# nanopositioner.net
KiCad netlist of a schematic drawn in EAGLE
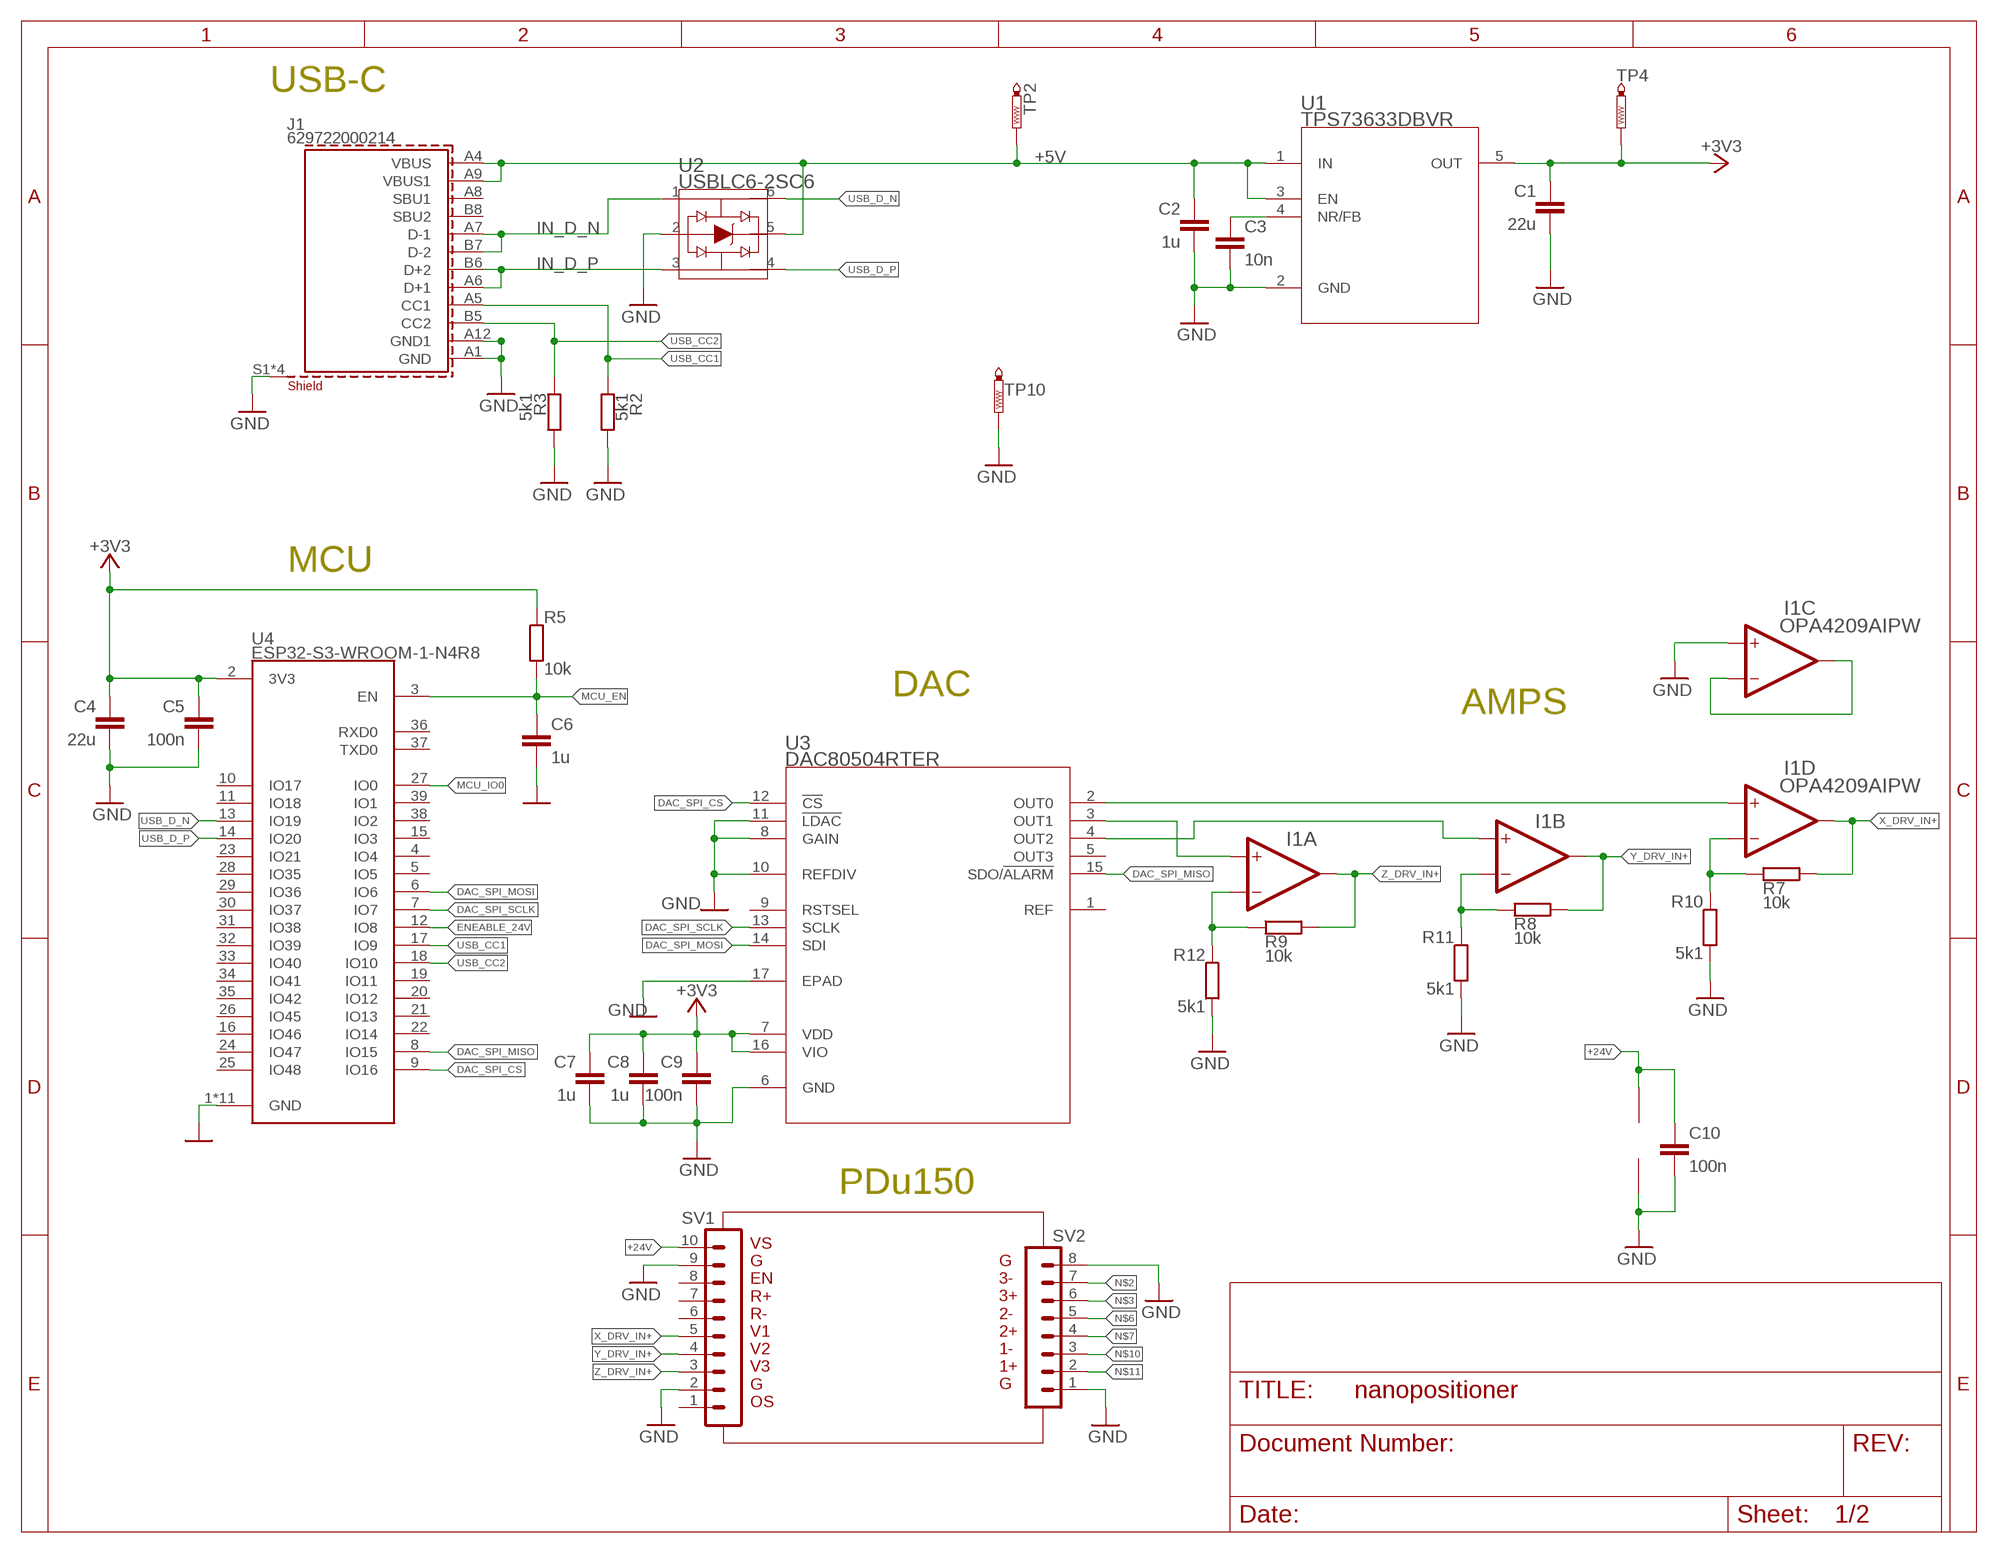
[diagram p0: schematic, sheet 1]
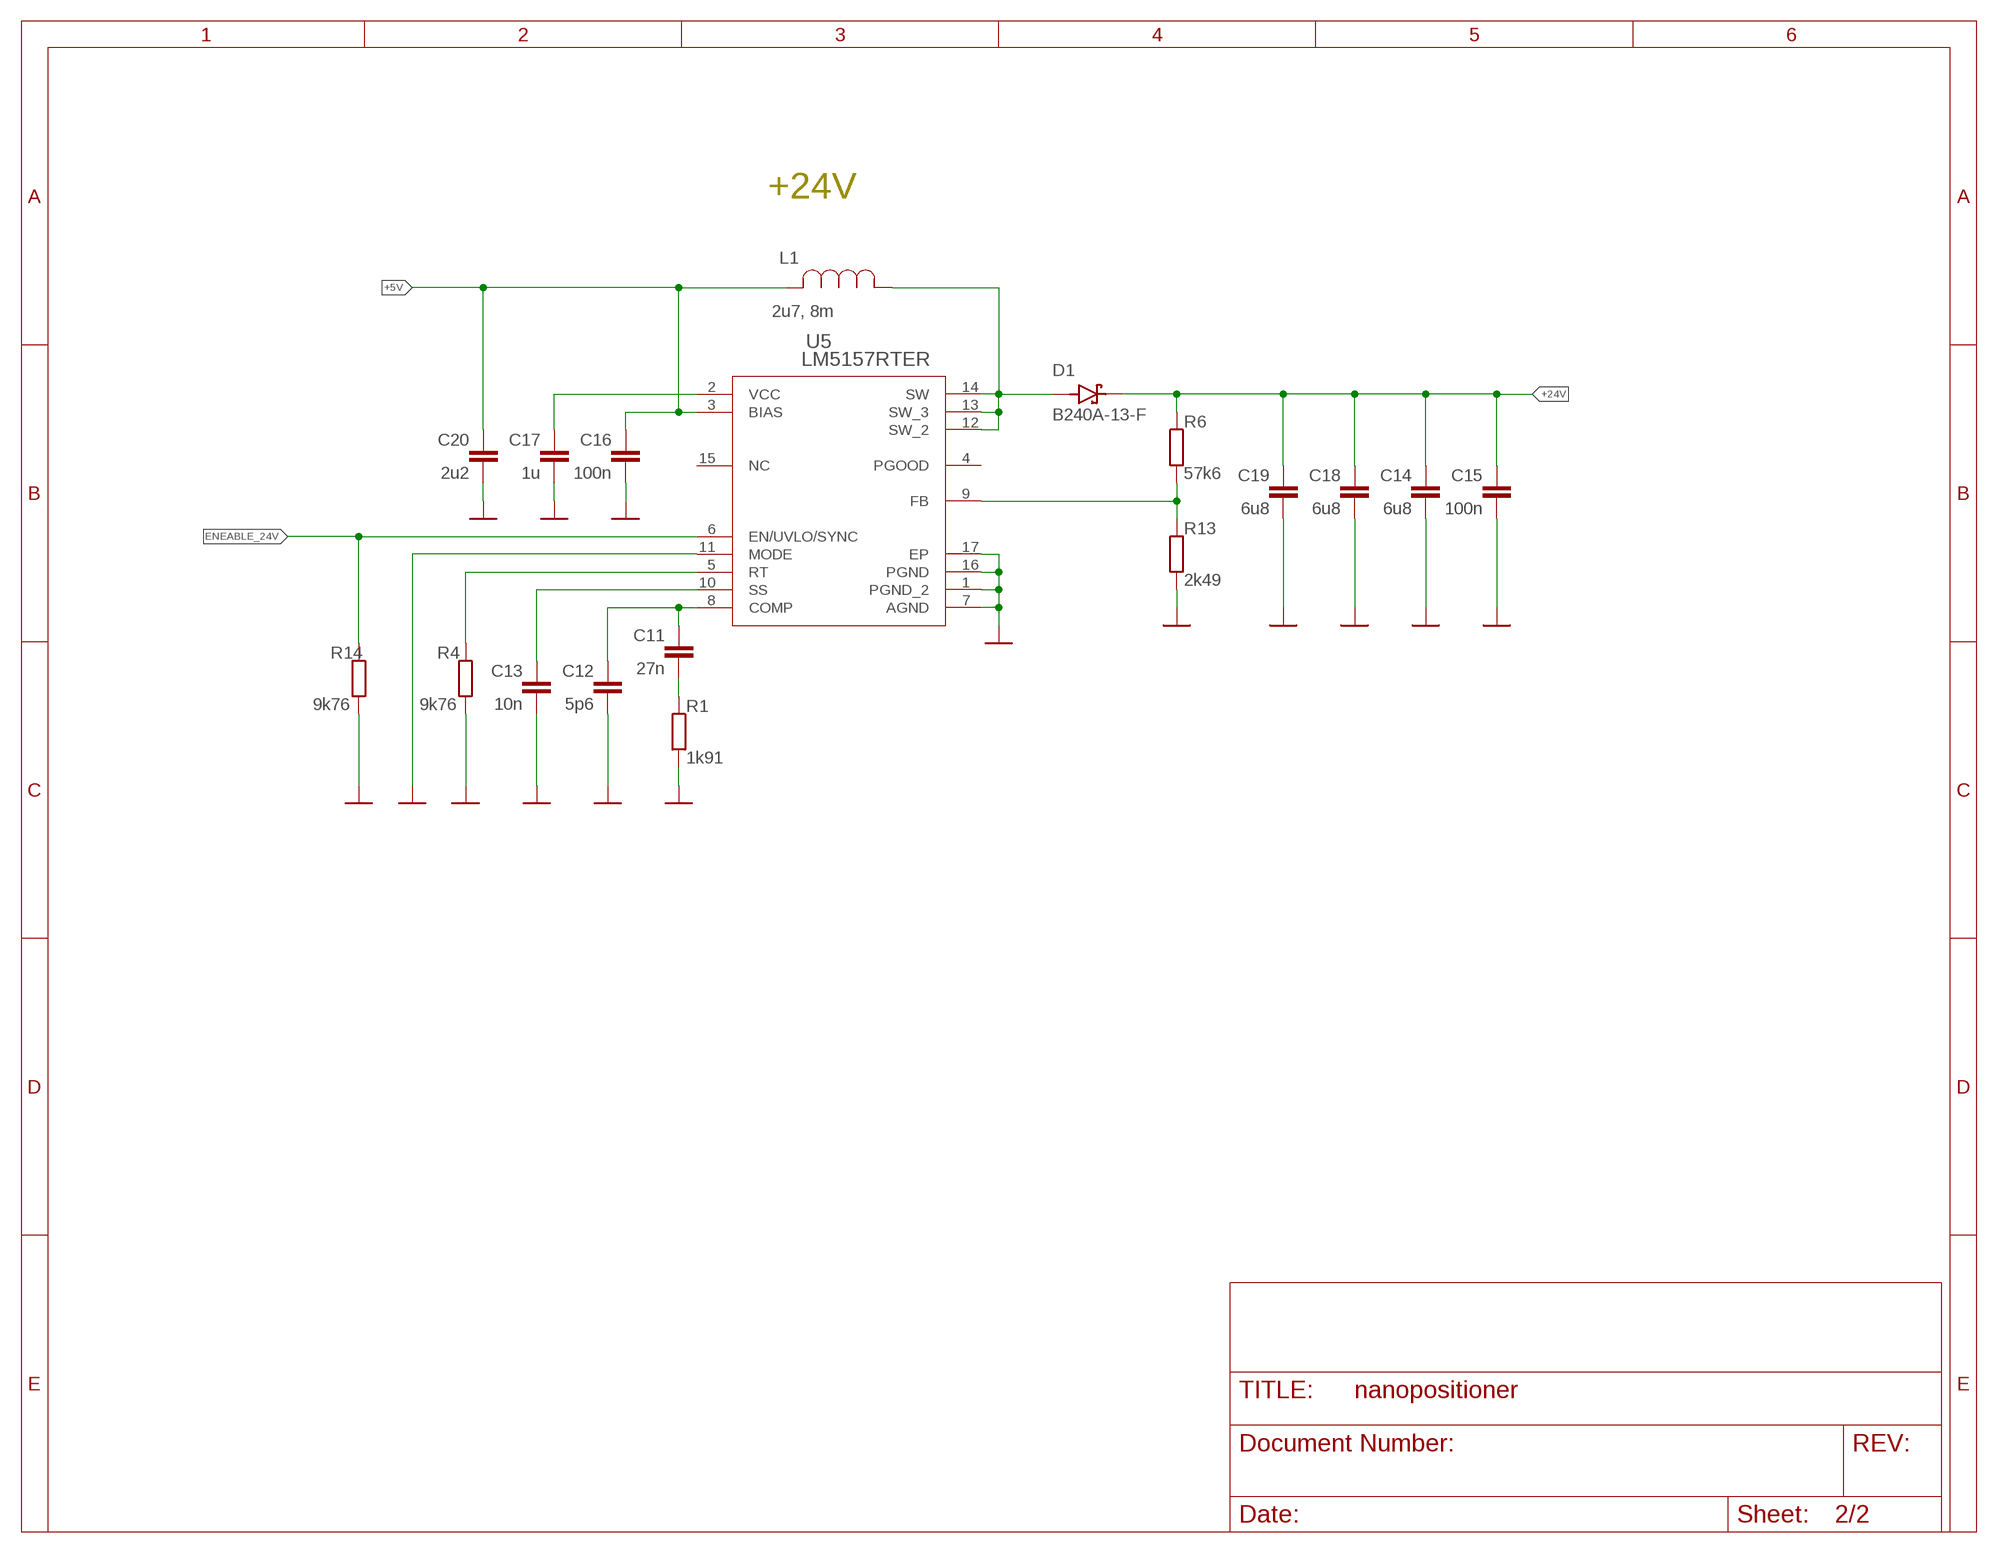
[diagram p1: schematic, sheet 2]

(export (version "E")
  (design (tool "Eeschema 10.0.6"))
  (components
    (comp (ref "C1")
      (value "22u")
      (footprint "eagle-import:C0603")
      (fields (field (name "MPN") "CL10A226MP8NUNE"))
      (libsource (lib "eagle-import") (part "C-EUC0603"))
    )
    (comp (ref "C2")
      (value "1u")
      (footprint "eagle-import:C0402")
      (fields (field (name "MPN") "GRM155R61E105MA12D"))
      (libsource (lib "eagle-import") (part "C-EUC0402"))
    )
    (comp (ref "C3")
      (value "10n")
      (footprint "eagle-import:C0402")
      (fields (field (name "MPN") "GCM155R71H103KA55D"))
      (libsource (lib "eagle-import") (part "C-EUC0402"))
    )
    (comp (ref "C4")
      (value "22u")
      (footprint "eagle-import:C0603")
      (fields (field (name "MPN") "CL10A226MP8NUNE"))
      (libsource (lib "eagle-import") (part "C-EUC0603"))
    )
    (comp (ref "C5")
      (value "100n")
      (footprint "eagle-import:C0402")
      (fields (field (name "MPN") "GRM155R71H104KE14D"))
      (libsource (lib "eagle-import") (part "C-EUC0402"))
    )
    (comp (ref "C6")
      (value "1u")
      (footprint "eagle-import:C0402")
      (fields (field (name "MPN") "GRM155R61E105MA12D"))
      (libsource (lib "eagle-import") (part "C-EUC0402"))
    )
    (comp (ref "C7")
      (value "1u")
      (footprint "eagle-import:C0402")
      (fields (field (name "MPN") "GRM155R61E105MA12D"))
      (libsource (lib "eagle-import") (part "C-EUC0402"))
    )
    (comp (ref "C8")
      (value "1u")
      (footprint "eagle-import:C0402")
      (fields (field (name "MPN") "GRM155R61E105MA12D"))
      (libsource (lib "eagle-import") (part "C-EUC0402"))
    )
    (comp (ref "C9")
      (value "100n")
      (footprint "eagle-import:C0402")
      (fields (field (name "MPN") "GRM155R71H104KE14D"))
      (libsource (lib "eagle-import") (part "C-EUC0402"))
    )
    (comp (ref "C10")
      (value "100n")
      (footprint "eagle-import:C0402")
      (fields (field (name "MPN") "GRM155R71H104KE14D"))
      (libsource (lib "eagle-import") (part "C-EUC0402"))
    )
    (comp (ref "I1")
      (value "OPA4209AIPW")
      (footprint "eagle-import:PW14")
      (fields
        (field (name "MPN") "OPA4209AIPW")
        (field (name "SPICEPREFIX") "J")
        (field (name "COPYRIGHT") "Copyright (C) 2024 Ultra Librarian. All rights reserved.")
      )
      (libsource (lib "eagle-import") (part "OPA4209AIPW"))
    )
    (comp (ref "J1")
      (value "629722000214")
      (footprint "eagle-import:629722000214")
      (fields (field (name "MPN") "12402012E212A"))
      (libsource (lib "eagle-import") (part "629722000214"))
    )
    (comp (ref "R2")
      (value "5k1")
      (footprint "eagle-import:R0402")
      (fields (field (name "MPN") "ERA-2AEB512X"))
      (libsource (lib "eagle-import") (part "R-EU_R0402"))
    )
    (comp (ref "R3")
      (value "5k1")
      (footprint "eagle-import:R0402")
      (fields (field (name "MPN") "ERA-2AEB512X"))
      (libsource (lib "eagle-import") (part "R-EU_R0402"))
    )
    (comp (ref "R5")
      (value "10k")
      (footprint "eagle-import:R0402")
      (fields (field (name "MPN") "ERA-2AEB103X"))
      (libsource (lib "eagle-import") (part "R-EU_R0402"))
    )
    (comp (ref "R7")
      (value "10k")
      (footprint "eagle-import:R0402")
      (fields (field (name "MPN") "ERA-2AEB103X"))
      (libsource (lib "eagle-import") (part "R-EU_R0402"))
    )
    (comp (ref "R8")
      (value "10k")
      (footprint "eagle-import:R0402")
      (fields (field (name "MPN") "ERA-2AEB103X"))
      (libsource (lib "eagle-import") (part "R-EU_R0402"))
    )
    (comp (ref "R9")
      (value "10k")
      (footprint "eagle-import:R0402")
      (fields (field (name "MPN") "ERA-2AEB103X"))
      (libsource (lib "eagle-import") (part "R-EU_R0402"))
    )
    (comp (ref "R10")
      (value "5k1")
      (footprint "eagle-import:R0402")
      (fields (field (name "MPN") "ERA-2AEB512X"))
      (libsource (lib "eagle-import") (part "R-EU_R0402"))
    )
    (comp (ref "R11")
      (value "5k1")
      (footprint "eagle-import:R0402")
      (fields (field (name "MPN") "ERA-2AEB512X"))
      (libsource (lib "eagle-import") (part "R-EU_R0402"))
    )
    (comp (ref "R12")
      (value "5k1")
      (footprint "eagle-import:R0402")
      (fields (field (name "MPN") "ERA-2AEB512X"))
      (libsource (lib "eagle-import") (part "R-EU_R0402"))
    )
    (comp (ref "SV1")
      (value "MA10-1")
      (footprint "eagle-import:MA10-1")
      (libsource (lib "eagle-import") (part "MA10-1"))
    )
    (comp (ref "SV2")
      (value "MA08-1")
      (footprint "eagle-import:MA08-1")
      (libsource (lib "eagle-import") (part "MA08-1"))
    )
    (comp (ref "TP2")
      (value "PTR1PAD1-13")
      (footprint "eagle-import:P1-13")
      (libsource (lib "eagle-import") (part "PTR1PAD1-13"))
    )
    (comp (ref "TP4")
      (value "PTR1PAD1-13")
      (footprint "eagle-import:P1-13")
      (libsource (lib "eagle-import") (part "PTR1PAD1-13"))
    )
    (comp (ref "TP10")
      (value "PTR1PAD1-13")
      (footprint "eagle-import:P1-13")
      (libsource (lib "eagle-import") (part "PTR1PAD1-13"))
    )
    (comp (ref "U1")
      (value "TPS73633DBVR")
      (footprint "eagle-import:DBV5")
      (fields
        (field (name "MANUFACTURER_PART_NUMBER") "TPS73601DBVR")
        (field (name "COPYRIGHT") "Copyright (C) 2023 Ultra Librarian. All rights reserved.")
      )
      (libsource (lib "eagle-import") (part "TPS73633DBVR"))
    )
    (comp (ref "U2")
      (value "USBLC6-2SC6")
      (footprint "eagle-import:SOT23-6L_STM")
      (fields (field (name "COPYRIGHT") "Copyright (C) 2023 Ultra Librarian. All rights reserved."))
      (libsource (lib "eagle-import") (part "USBLC6-2SC6"))
    )
    (comp (ref "U3")
      (value "DAC80504RTER")
      (footprint "eagle-import:RTE16_TEX")
      (fields
        (field (name "MPN") "DAC80504RTET")
        (field (name "COPYRIGHT") "Copyright (C) 2024 Ultra Librarian. All rights reserved.")
      )
      (libsource (lib "eagle-import") (part "DAC80504RTER"))
    )
    (comp (ref "U4")
      (value "ESP32-S3-WROOM-1-N4R8")
      (footprint "eagle-import:XCVR_ESP32S3WROOM1N8R8")
      (fields
        (field (name "MF") "Espressif Systems")
        (field (name "MP") "ESP32-S3-WROOM-1-N8R8")
        (field (name "MPN") "ESP32-S3-WROOM-1-N4")
      )
      (libsource (lib "eagle-import") (part "ESP32-S3-WROOM-1-N4R8"))
    )
    (comp (ref "C11")
      (value "27n")
      (footprint "eagle-import:C0402")
      (fields (field (name "MPN") "GRM155R71A273KA01D"))
      (libsource (lib "eagle-import") (part "C-EUC0402"))
    )
    (comp (ref "C12")
      (value "5p6")
      (footprint "eagle-import:C0402")
      (fields (field (name "MPN") "GRM1555C1H5R6CA01D"))
      (libsource (lib "eagle-import") (part "C-EUC0402"))
    )
    (comp (ref "C13")
      (value "10n")
      (footprint "eagle-import:C0402")
      (fields (field (name "MPN") "GRM033R70J103KA01D"))
      (libsource (lib "eagle-import") (part "C-EUC0402"))
    )
    (comp (ref "C14")
      (value "6u8")
      (footprint "eagle-import:C1206")
      (fields (field (name "MPN") "C3216X5R1H685K160AB"))
      (libsource (lib "eagle-import") (part "C-EUC1206"))
    )
    (comp (ref "C15")
      (value "100n")
      (footprint "eagle-import:C0603")
      (fields (field (name "MPN") "CGA3E2X7R1H104K080AA"))
      (libsource (lib "eagle-import") (part "C-EUC0603"))
    )
    (comp (ref "C16")
      (value "100n")
      (footprint "eagle-import:C0603")
      (fields (field (name "MPN") "KGM21NR71E104KT"))
      (libsource (lib "eagle-import") (part "C-EUC0603"))
    )
    (comp (ref "C17")
      (value "1u")
      (footprint "eagle-import:C0402")
      (fields (field (name "MPN") "EMK107B7105KA-T"))
      (libsource (lib "eagle-import") (part "C-EUC0402"))
    )
    (comp (ref "C18")
      (value "6u8")
      (footprint "eagle-import:C1206")
      (fields (field (name "MPN") "C3216X5R1H685K160AB"))
      (libsource (lib "eagle-import") (part "C-EUC1206"))
    )
    (comp (ref "C19")
      (value "6u8")
      (footprint "eagle-import:C1206")
      (fields (field (name "MPN") "C3216X5R1H685K160AB"))
      (libsource (lib "eagle-import") (part "C-EUC1206"))
    )
    (comp (ref "C20")
      (value "2u2")
      (footprint "eagle-import:C0805")
      (fields (field (name "MPN") "GRM21BR71A225KA01L"))
      (libsource (lib "eagle-import") (part "C-EUC0805"))
    )
    (comp (ref "D1")
      (value "B240A-13-F")
      (footprint "eagle-import:DIOM5226X230N")
      (fields (field (name "MANUFACTURER") "Diodes"))
      (libsource (lib "eagle-import") (part "B240A-13-F"))
    )
    (comp (ref "L1")
      (value "2u7, 8m")
      (footprint "eagle-import:IND_BOURNS_SDR1307")
      (fields (field (name "MPN") "SDR1307-2R7ML"))
      (libsource (lib "eagle-import") (part "SDR1307-2R7ML"))
    )
    (comp (ref "R1")
      (value "1k91")
      (footprint "eagle-import:R0402")
      (fields (field (name "MPN") "CRCW04021K91FKED"))
      (libsource (lib "eagle-import") (part "R-EU_R0402"))
    )
    (comp (ref "R4")
      (value "9k76")
      (footprint "eagle-import:R0402")
      (fields (field (name "MPN") "CRCW04029K76FKED"))
      (libsource (lib "eagle-import") (part "R-EU_R0402"))
    )
    (comp (ref "R6")
      (value "57k6")
      (footprint "eagle-import:R0402")
      (fields (field (name "MPN") "CRCW040257K6FKED"))
      (libsource (lib "eagle-import") (part "R-EU_R0402"))
    )
    (comp (ref "R13")
      (value "2k49")
      (footprint "eagle-import:R0402")
      (fields (field (name "MPN") "CRCW04022K49FKED"))
      (libsource (lib "eagle-import") (part "R-EU_R0402"))
    )
    (comp (ref "R14")
      (value "9k76")
      (footprint "eagle-import:R0402")
      (fields (field (name "MPN") "CRCW04029K76FKED"))
      (libsource (lib "eagle-import") (part "R-EU_R0402"))
    )
    (comp (ref "U5")
      (value "LM5157RTER")
      (footprint "eagle-import:QFN_57RTER_TEX")
      (fields (field (name "COPYRIGHT") "Copyright (C) 2024 Ultra Librarian. All rights reserved."))
      (libsource (lib "eagle-import") (part "LM5157RTER"))
    )
  )
  (nets
    (net (code "1") (name "+3V3") (class "Default")
      (node (ref "C1") (pin "1") (pinfunction "1_1") (pintype "passive"))
      (node (ref "C4") (pin "1") (pinfunction "1_1") (pintype "passive"))
      (node (ref "C5") (pin "1") (pinfunction "1_1") (pintype "passive"))
      (node (ref "C7") (pin "1") (pinfunction "1_1") (pintype "passive"))
      (node (ref "C8") (pin "1") (pinfunction "1_1") (pintype "passive"))
      (node (ref "C9") (pin "1") (pinfunction "1_1") (pintype "passive"))
      (node (ref "R5") (pin "1") (pinfunction "1_1") (pintype "passive"))
      (node (ref "TP4") (pin "TP") (pinfunction "TP_TP") (pintype "input"))
      (node (ref "U1") (pin "5") (pinfunction "OUT_5") (pintype "output"))
      (node (ref "U3") (pin "16") (pinfunction "VIO_16") (pintype "power_in"))
      (node (ref "U3") (pin "7") (pinfunction "VDD_7") (pintype "power_in"))
      (node (ref "U4") (pin "2") (pinfunction "3V3_2") (pintype "power_in"))
    )
    (net (code "2") (name "+5V") (class "Default")
      (node (ref "C16") (pin "2") (pinfunction "2_2") (pintype "passive"))
      (node (ref "C2") (pin "2") (pinfunction "2_2") (pintype "passive"))
      (node (ref "C20") (pin "2") (pinfunction "2_2") (pintype "passive"))
      (node (ref "J1") (pin "A4") (pinfunction "VBUS_A4") (pintype "passive"))
      (node (ref "J1") (pin "A9") (pinfunction "VBUS1_A9") (pintype "passive"))
      (node (ref "L1") (pin "2") (pinfunction "2_2") (pintype "passive"))
      (node (ref "TP2") (pin "TP") (pinfunction "TP_TP") (pintype "input"))
      (node (ref "U1") (pin "1") (pinfunction "IN_1") (pintype "input"))
      (node (ref "U1") (pin "3") (pinfunction "EN_3") (pintype "passive"))
      (node (ref "U2") (pin "5") (pinfunction "5_5") (pintype "passive"))
      (node (ref "U5") (pin "3") (pinfunction "BIAS_3") (pintype "passive"))
    )
    (net (code "3") (name "+24V") (class "Default")
      (node (ref "C10") (pin "1") (pinfunction "1_1") (pintype "passive"))
      (node (ref "C14") (pin "2") (pinfunction "2_2") (pintype "passive"))
      (node (ref "C15") (pin "2") (pinfunction "2_2") (pintype "passive"))
      (node (ref "C18") (pin "2") (pinfunction "2_2") (pintype "passive"))
      (node (ref "C19") (pin "2") (pinfunction "2_2") (pintype "passive"))
      (node (ref "D1") (pin "C") (pinfunction "K_C") (pintype "passive"))
      (node (ref "I1") (pin "4") (pinfunction "P$1_4") (pintype "bidirectional"))
      (node (ref "R6") (pin "1") (pinfunction "1_1") (pintype "passive"))
      (node (ref "SV1") (pin "10") (pinfunction "10_10") (pintype "passive"))
    )
    (net (code "4") (name "DAC_SPI_CS") (class "Default")
      (node (ref "U3") (pin "12") (pinfunction "~{CS}_12") (pintype "input"))
      (node (ref "U4") (pin "9") (pinfunction "IO16_9") (pintype "bidirectional"))
    )
    (net (code "5") (name "DAC_SPI_MISO") (class "Default")
      (node (ref "U3") (pin "15") (pinfunction "SDO/~{ALARM}_15") (pintype "output"))
      (node (ref "U4") (pin "8") (pinfunction "IO15_8") (pintype "bidirectional"))
    )
    (net (code "6") (name "DAC_SPI_MOSI") (class "Default")
      (node (ref "U3") (pin "14") (pinfunction "SDI_14") (pintype "input"))
      (node (ref "U4") (pin "6") (pinfunction "IO6_6") (pintype "bidirectional"))
    )
    (net (code "7") (name "DAC_SPI_SCLK") (class "Default")
      (node (ref "U3") (pin "13") (pinfunction "SCLK_13") (pintype "input"))
      (node (ref "U4") (pin "7") (pinfunction "IO7_7") (pintype "bidirectional"))
    )
    (net (code "8") (name "ENEABLE_24V") (class "Default")
      (node (ref "R14") (pin "1") (pinfunction "1_1") (pintype "passive"))
      (node (ref "U4") (pin "12") (pinfunction "IO8_12") (pintype "bidirectional"))
      (node (ref "U5") (pin "6") (pinfunction "EN/UVLO/SYNC_6") (pintype "passive"))
    )
    (net (code "9") (name "GND") (class "Default")
      (node (ref "C1") (pin "2") (pinfunction "2_2") (pintype "passive"))
      (node (ref "C10") (pin "2") (pinfunction "2_2") (pintype "passive"))
      (node (ref "C12") (pin "1") (pinfunction "1_1") (pintype "passive"))
      (node (ref "C13") (pin "1") (pinfunction "1_1") (pintype "passive"))
      (node (ref "C14") (pin "1") (pinfunction "1_1") (pintype "passive"))
      (node (ref "C15") (pin "1") (pinfunction "1_1") (pintype "passive"))
      (node (ref "C16") (pin "1") (pinfunction "1_1") (pintype "passive"))
      (node (ref "C17") (pin "1") (pinfunction "1_1") (pintype "passive"))
      (node (ref "C18") (pin "1") (pinfunction "1_1") (pintype "passive"))
      (node (ref "C19") (pin "1") (pinfunction "1_1") (pintype "passive"))
      (node (ref "C2") (pin "1") (pinfunction "1_1") (pintype "passive"))
      (node (ref "C20") (pin "1") (pinfunction "1_1") (pintype "passive"))
      (node (ref "C3") (pin "2") (pinfunction "2_2") (pintype "passive"))
      (node (ref "C4") (pin "2") (pinfunction "2_2") (pintype "passive"))
      (node (ref "C5") (pin "2") (pinfunction "2_2") (pintype "passive"))
      (node (ref "C6") (pin "1") (pinfunction "1_1") (pintype "passive"))
      (node (ref "C7") (pin "2") (pinfunction "2_2") (pintype "passive"))
      (node (ref "C8") (pin "2") (pinfunction "2_2") (pintype "passive"))
      (node (ref "C9") (pin "2") (pinfunction "2_2") (pintype "passive"))
      (node (ref "I1") (pin "10") (pinfunction "INA+_10") (pintype "input"))
      (node (ref "I1") (pin "11") (pinfunction "P$2_11") (pintype "bidirectional"))
      (node (ref "J1") (pin "A1") (pinfunction "GND_A1") (pintype "passive"))
      (node (ref "J1") (pin "A12") (pinfunction "GND1_A12") (pintype "passive"))
      (node (ref "J1") (pin "S1") (pinfunction "SHIELD_S1") (pintype "passive"))
      (node (ref "J1") (pin "S2") (pinfunction "SHIELD_S2") (pintype "passive"))
      (node (ref "J1") (pin "S3") (pinfunction "SHIELD_S3") (pintype "passive"))
      (node (ref "J1") (pin "S4") (pinfunction "SHIELD_S4") (pintype "passive"))
      (node (ref "R1") (pin "2") (pinfunction "2_2") (pintype "passive"))
      (node (ref "R10") (pin "2") (pinfunction "2_2") (pintype "passive"))
      (node (ref "R11") (pin "2") (pinfunction "2_2") (pintype "passive"))
      (node (ref "R12") (pin "2") (pinfunction "2_2") (pintype "passive"))
      (node (ref "R13") (pin "2") (pinfunction "2_2") (pintype "passive"))
      (node (ref "R14") (pin "2") (pinfunction "2_2") (pintype "passive"))
      (node (ref "R2") (pin "1") (pinfunction "1_1") (pintype "passive"))
      (node (ref "R3") (pin "2") (pinfunction "2_2") (pintype "passive"))
      (node (ref "R4") (pin "2") (pinfunction "2_2") (pintype "passive"))
      (node (ref "SV1") (pin "2") (pinfunction "2_2") (pintype "passive"))
      (node (ref "SV1") (pin "9") (pinfunction "9_9") (pintype "passive"))
      (node (ref "SV2") (pin "1") (pinfunction "1_1") (pintype "passive"))
      (node (ref "SV2") (pin "8") (pinfunction "8_8") (pintype "passive"))
      (node (ref "TP10") (pin "TP") (pinfunction "TP_TP") (pintype "input"))
      (node (ref "U1") (pin "2") (pinfunction "GND_2") (pintype "power_in"))
      (node (ref "U2") (pin "2") (pinfunction "2_2") (pintype "passive"))
      (node (ref "U3") (pin "10") (pinfunction "REFDIV_10") (pintype "input"))
      (node (ref "U3") (pin "11") (pinfunction "~{LDAC}_11") (pintype "input"))
      (node (ref "U3") (pin "17") (pinfunction "EPAD_17") (pintype "passive"))
      (node (ref "U3") (pin "6") (pinfunction "GND_6") (pintype "power_in"))
      (node (ref "U3") (pin "8") (pinfunction "GAIN_8") (pintype "input"))
      (node (ref "U4") (pin "1") (pinfunction "GND_1") (pintype "power_in"))
      (node (ref "U4") (pin "40") (pinfunction "GND_40") (pintype "power_in"))
      (node (ref "U4") (pin "41_1") (pinfunction "GND_41_1") (pintype "power_in"))
      (node (ref "U4") (pin "41_2") (pinfunction "GND_41_2") (pintype "power_in"))
      (node (ref "U4") (pin "41_3") (pinfunction "GND_41_3") (pintype "power_in"))
      (node (ref "U4") (pin "41_4") (pinfunction "GND_41_4") (pintype "power_in"))
      (node (ref "U4") (pin "41_5") (pinfunction "GND_41_5") (pintype "power_in"))
      (node (ref "U4") (pin "41_6") (pinfunction "GND_41_6") (pintype "power_in"))
      (node (ref "U4") (pin "41_7") (pinfunction "GND_41_7") (pintype "power_in"))
      (node (ref "U4") (pin "41_8") (pinfunction "GND_41_8") (pintype "power_in"))
      (node (ref "U4") (pin "41_9") (pinfunction "GND_41_9") (pintype "power_in"))
      (node (ref "U5") (pin "1") (pinfunction "PGND_2_1") (pintype "passive"))
      (node (ref "U5") (pin "11") (pinfunction "MODE_11") (pintype "passive"))
      (node (ref "U5") (pin "16") (pinfunction "PGND_16") (pintype "passive"))
      (node (ref "U5") (pin "17") (pinfunction "EP_17") (pintype "passive"))
      (node (ref "U5") (pin "7") (pinfunction "AGND_7") (pintype "passive"))
    )
    (net (code "10") (name "IN_D_N") (class "Default")
      (node (ref "J1") (pin "A7") (pinfunction "D-1_A7") (pintype "passive"))
      (node (ref "J1") (pin "B7") (pinfunction "D-2_B7") (pintype "passive"))
      (node (ref "U2") (pin "1") (pinfunction "1_1") (pintype "passive"))
    )
    (net (code "11") (name "IN_D_P") (class "Default")
      (node (ref "J1") (pin "A6") (pinfunction "D+1_A6") (pintype "passive"))
      (node (ref "J1") (pin "B6") (pinfunction "D+2_B6") (pintype "passive"))
      (node (ref "U2") (pin "3") (pinfunction "3_3") (pintype "passive"))
    )
    (net (code "12") (name "MCU_EN") (class "Default")
      (node (ref "C6") (pin "2") (pinfunction "2_2") (pintype "passive"))
      (node (ref "R5") (pin "2") (pinfunction "2_2") (pintype "passive"))
      (node (ref "U4") (pin "3") (pinfunction "EN_3") (pintype "input"))
    )
    (net (code "13") (name "MCU_IO0") (class "Default")
      (node (ref "U4") (pin "27") (pinfunction "IO0_27") (pintype "bidirectional"))
    )
    (net (code "14") (name "N$2") (class "Default")
      (node (ref "SV2") (pin "7") (pinfunction "7_7") (pintype "passive"))
    )
    (net (code "15") (name "N$3") (class "Default")
      (node (ref "SV2") (pin "6") (pinfunction "6_6") (pintype "passive"))
    )
    (net (code "16") (name "N$6") (class "Default")
      (node (ref "SV2") (pin "5") (pinfunction "5_5") (pintype "passive"))
    )
    (net (code "17") (name "N$7") (class "Default")
      (node (ref "SV2") (pin "4") (pinfunction "4_4") (pintype "passive"))
    )
    (net (code "18") (name "N$10") (class "Default")
      (node (ref "SV2") (pin "3") (pinfunction "3_3") (pintype "passive"))
    )
    (net (code "19") (name "N$11") (class "Default")
      (node (ref "SV2") (pin "2") (pinfunction "2_2") (pintype "passive"))
    )
    (net (code "20") (name "Net-(C11-Pad1)") (class "Default")
      (node (ref "C11") (pin "1") (pinfunction "1_1") (pintype "passive"))
      (node (ref "R1") (pin "1") (pinfunction "1_1") (pintype "passive"))
    )
    (net (code "21") (name "Net-(I1A-INA+)") (class "Default")
      (node (ref "I1") (pin "3") (pinfunction "INA+_3") (pintype "input"))
      (node (ref "U3") (pin "3") (pinfunction "OUT1_3") (pintype "output"))
    )
    (net (code "22") (name "Net-(I1A-INA-)") (class "Default")
      (node (ref "I1") (pin "2") (pinfunction "INA-_2") (pintype "input"))
      (node (ref "R12") (pin "1") (pinfunction "1_1") (pintype "passive"))
      (node (ref "R9") (pin "1") (pinfunction "1_1") (pintype "passive"))
    )
    (net (code "23") (name "Net-(I1B-INA+)") (class "Default")
      (node (ref "I1") (pin "5") (pinfunction "INA+_5") (pintype "input"))
      (node (ref "U3") (pin "4") (pinfunction "OUT2_4") (pintype "output"))
    )
    (net (code "24") (name "Net-(I1B-INA-)") (class "Default")
      (node (ref "I1") (pin "6") (pinfunction "INA-_6") (pintype "input"))
      (node (ref "R11") (pin "1") (pinfunction "1_1") (pintype "passive"))
      (node (ref "R8") (pin "1") (pinfunction "1_1") (pintype "passive"))
    )
    (net (code "25") (name "Net-(I1C-INA-)") (class "Default")
      (node (ref "I1") (pin "8") (pinfunction "OUTA_8") (pintype "output"))
      (node (ref "I1") (pin "9") (pinfunction "INA-_9") (pintype "input"))
    )
    (net (code "26") (name "Net-(I1D-INA+)") (class "Default")
      (node (ref "I1") (pin "12") (pinfunction "INA+_12") (pintype "input"))
      (node (ref "U3") (pin "2") (pinfunction "OUT0_2") (pintype "output"))
    )
    (net (code "27") (name "Net-(I1D-INA-)") (class "Default")
      (node (ref "I1") (pin "13") (pinfunction "INA-_13") (pintype "input"))
      (node (ref "R10") (pin "1") (pinfunction "1_1") (pintype "passive"))
      (node (ref "R7") (pin "1") (pinfunction "1_1") (pintype "passive"))
    )
    (net (code "28") (name "Net-(U1-NR{slash}FB)") (class "Default")
      (node (ref "C3") (pin "1") (pinfunction "1_1") (pintype "passive"))
      (node (ref "U1") (pin "4") (pinfunction "NR/FB_4") (pintype "bidirectional"))
    )
    (net (code "29") (name "Net-(U5-COMP)") (class "Default")
      (node (ref "C11") (pin "2") (pinfunction "2_2") (pintype "passive"))
      (node (ref "C12") (pin "2") (pinfunction "2_2") (pintype "passive"))
      (node (ref "U5") (pin "8") (pinfunction "COMP_8") (pintype "passive"))
    )
    (net (code "30") (name "Net-(U5-FB)") (class "Default")
      (node (ref "R13") (pin "1") (pinfunction "1_1") (pintype "passive"))
      (node (ref "R6") (pin "2") (pinfunction "2_2") (pintype "passive"))
      (node (ref "U5") (pin "9") (pinfunction "FB_9") (pintype "passive"))
    )
    (net (code "31") (name "Net-(U5-RT)") (class "Default")
      (node (ref "R4") (pin "1") (pinfunction "1_1") (pintype "passive"))
      (node (ref "U5") (pin "5") (pinfunction "RT_5") (pintype "passive"))
    )
    (net (code "32") (name "Net-(U5-SS)") (class "Default")
      (node (ref "C13") (pin "2") (pinfunction "2_2") (pintype "passive"))
      (node (ref "U5") (pin "10") (pinfunction "SS_10") (pintype "passive"))
    )
    (net (code "33") (name "Net-(U5-SW)") (class "Default")
      (node (ref "D1") (pin "A") (pinfunction "A_A") (pintype "passive"))
      (node (ref "L1") (pin "1") (pinfunction "1_1") (pintype "passive"))
      (node (ref "U5") (pin "12") (pinfunction "SW_2_12") (pintype "passive"))
      (node (ref "U5") (pin "13") (pinfunction "SW_3_13") (pintype "passive"))
      (node (ref "U5") (pin "14") (pinfunction "SW_14") (pintype "passive"))
    )
    (net (code "34") (name "Net-(U5-VCC)") (class "Default")
      (node (ref "C17") (pin "2") (pinfunction "2_2") (pintype "passive"))
      (node (ref "U5") (pin "2") (pinfunction "VCC_2") (pintype "power_in"))
    )
    (net (code "35") (name "PGOOD") (class "Default")
      (node (ref "U5") (pin "4") (pinfunction "PGOOD_4") (pintype "power_in"))
    )
    (net (code "36") (name "USB_CC1") (class "Default")
      (node (ref "J1") (pin "A5") (pinfunction "CC1_A5") (pintype "passive"))
      (node (ref "R2") (pin "2") (pinfunction "2_2") (pintype "passive"))
      (node (ref "U4") (pin "17") (pinfunction "IO9_17") (pintype "bidirectional"))
    )
    (net (code "37") (name "USB_CC2") (class "Default")
      (node (ref "J1") (pin "B5") (pinfunction "CC2_B5") (pintype "passive"))
      (node (ref "R3") (pin "1") (pinfunction "1_1") (pintype "passive"))
      (node (ref "U4") (pin "18") (pinfunction "IO10_18") (pintype "bidirectional"))
    )
    (net (code "38") (name "USB_D_N") (class "Default")
      (node (ref "U2") (pin "6") (pinfunction "6_6") (pintype "passive"))
      (node (ref "U4") (pin "13") (pinfunction "IO19_13") (pintype "bidirectional"))
    )
    (net (code "39") (name "USB_D_P") (class "Default")
      (node (ref "U2") (pin "4") (pinfunction "4_4") (pintype "passive"))
      (node (ref "U4") (pin "14") (pinfunction "IO20_14") (pintype "bidirectional"))
    )
    (net (code "40") (name "X_DRV_IN+") (class "Default")
      (node (ref "I1") (pin "14") (pinfunction "OUTA_14") (pintype "output"))
      (node (ref "R7") (pin "2") (pinfunction "2_2") (pintype "passive"))
      (node (ref "SV1") (pin "5") (pinfunction "5_5") (pintype "passive"))
    )
    (net (code "41") (name "Y_DRV_IN+") (class "Default")
      (node (ref "I1") (pin "7") (pinfunction "OUTA_7") (pintype "output"))
      (node (ref "R8") (pin "2") (pinfunction "2_2") (pintype "passive"))
      (node (ref "SV1") (pin "4") (pinfunction "4_4") (pintype "passive"))
    )
    (net (code "42") (name "Z_DRV_IN+") (class "Default")
      (node (ref "I1") (pin "1") (pinfunction "OUTA_1") (pintype "output"))
      (node (ref "R9") (pin "2") (pinfunction "2_2") (pintype "passive"))
      (node (ref "SV1") (pin "3") (pinfunction "3_3") (pintype "passive"))
    )
    (net (code "43") (name "unconnected-(J1-SBU1-PadA8)") (class "Default")
      (node (ref "J1") (pin "A8") (pinfunction "SBU1_A8") (pintype "passive"))
    )
    (net (code "44") (name "unconnected-(J1-SBU2-PadB8)") (class "Default")
      (node (ref "J1") (pin "B8") (pinfunction "SBU2_B8") (pintype "passive"))
    )
    (net (code "45") (name "unconnected-(SV1-Pad1)") (class "Default")
      (node (ref "SV1") (pin "1") (pinfunction "1_1") (pintype "passive"))
    )
    (net (code "46") (name "unconnected-(SV1-Pad6)") (class "Default")
      (node (ref "SV1") (pin "6") (pinfunction "6_6") (pintype "passive"))
    )
    (net (code "47") (name "unconnected-(SV1-Pad7)") (class "Default")
      (node (ref "SV1") (pin "7") (pinfunction "7_7") (pintype "passive"))
    )
    (net (code "48") (name "unconnected-(SV1-Pad8)") (class "Default")
      (node (ref "SV1") (pin "8") (pinfunction "8_8") (pintype "passive"))
    )
    (net (code "49") (name "unconnected-(U3-OUT3-Pad5)") (class "Default")
      (node (ref "U3") (pin "5") (pinfunction "OUT3_5") (pintype "output"))
    )
    (net (code "50") (name "unconnected-(U3-REF-Pad1)") (class "Default")
      (node (ref "U3") (pin "1") (pinfunction "REF_1") (pintype "bidirectional"))
    )
    (net (code "51") (name "unconnected-(U3-RSTSEL-Pad9)") (class "Default")
      (node (ref "U3") (pin "9") (pinfunction "RSTSEL_9") (pintype "input"))
    )
    (net (code "52") (name "unconnected-(U4-IO1-Pad39)") (class "Default")
      (node (ref "U4") (pin "39") (pinfunction "IO1_39") (pintype "bidirectional"))
    )
    (net (code "53") (name "unconnected-(U4-IO2-Pad38)") (class "Default")
      (node (ref "U4") (pin "38") (pinfunction "IO2_38") (pintype "bidirectional"))
    )
    (net (code "54") (name "unconnected-(U4-IO3-Pad15)") (class "Default")
      (node (ref "U4") (pin "15") (pinfunction "IO3_15") (pintype "bidirectional"))
    )
    (net (code "55") (name "unconnected-(U4-IO4-Pad4)") (class "Default")
      (node (ref "U4") (pin "4") (pinfunction "IO4_4") (pintype "bidirectional"))
    )
    (net (code "56") (name "unconnected-(U4-IO5-Pad5)") (class "Default")
      (node (ref "U4") (pin "5") (pinfunction "IO5_5") (pintype "bidirectional"))
    )
    (net (code "57") (name "unconnected-(U4-IO11-Pad19)") (class "Default")
      (node (ref "U4") (pin "19") (pinfunction "IO11_19") (pintype "bidirectional"))
    )
    (net (code "58") (name "unconnected-(U4-IO12-Pad20)") (class "Default")
      (node (ref "U4") (pin "20") (pinfunction "IO12_20") (pintype "bidirectional"))
    )
    (net (code "59") (name "unconnected-(U4-IO13-Pad21)") (class "Default")
      (node (ref "U4") (pin "21") (pinfunction "IO13_21") (pintype "bidirectional"))
    )
    (net (code "60") (name "unconnected-(U4-IO14-Pad22)") (class "Default")
      (node (ref "U4") (pin "22") (pinfunction "IO14_22") (pintype "bidirectional"))
    )
    (net (code "61") (name "unconnected-(U4-IO17-Pad10)") (class "Default")
      (node (ref "U4") (pin "10") (pinfunction "IO17_10") (pintype "bidirectional"))
    )
    (net (code "62") (name "unconnected-(U4-IO18-Pad11)") (class "Default")
      (node (ref "U4") (pin "11") (pinfunction "IO18_11") (pintype "bidirectional"))
    )
    (net (code "63") (name "unconnected-(U4-IO21-Pad23)") (class "Default")
      (node (ref "U4") (pin "23") (pinfunction "IO21_23") (pintype "bidirectional"))
    )
    (net (code "64") (name "unconnected-(U4-IO35-Pad28)") (class "Default")
      (node (ref "U4") (pin "28") (pinfunction "IO35_28") (pintype "bidirectional"))
    )
    (net (code "65") (name "unconnected-(U4-IO36-Pad29)") (class "Default")
      (node (ref "U4") (pin "29") (pinfunction "IO36_29") (pintype "bidirectional"))
    )
    (net (code "66") (name "unconnected-(U4-IO37-Pad30)") (class "Default")
      (node (ref "U4") (pin "30") (pinfunction "IO37_30") (pintype "bidirectional"))
    )
    (net (code "67") (name "unconnected-(U4-IO38-Pad31)") (class "Default")
      (node (ref "U4") (pin "31") (pinfunction "IO38_31") (pintype "bidirectional"))
    )
    (net (code "68") (name "unconnected-(U4-IO39-Pad32)") (class "Default")
      (node (ref "U4") (pin "32") (pinfunction "IO39_32") (pintype "bidirectional"))
    )
    (net (code "69") (name "unconnected-(U4-IO40-Pad33)") (class "Default")
      (node (ref "U4") (pin "33") (pinfunction "IO40_33") (pintype "bidirectional"))
    )
    (net (code "70") (name "unconnected-(U4-IO41-Pad34)") (class "Default")
      (node (ref "U4") (pin "34") (pinfunction "IO41_34") (pintype "bidirectional"))
    )
    (net (code "71") (name "unconnected-(U4-IO42-Pad35)") (class "Default")
      (node (ref "U4") (pin "35") (pinfunction "IO42_35") (pintype "bidirectional"))
    )
    (net (code "72") (name "unconnected-(U4-IO45-Pad26)") (class "Default")
      (node (ref "U4") (pin "26") (pinfunction "IO45_26") (pintype "bidirectional"))
    )
    (net (code "73") (name "unconnected-(U4-IO46-Pad16)") (class "Default")
      (node (ref "U4") (pin "16") (pinfunction "IO46_16") (pintype "bidirectional"))
    )
    (net (code "74") (name "unconnected-(U4-IO47-Pad24)") (class "Default")
      (node (ref "U4") (pin "24") (pinfunction "IO47_24") (pintype "bidirectional"))
    )
    (net (code "75") (name "unconnected-(U4-IO48-Pad25)") (class "Default")
      (node (ref "U4") (pin "25") (pinfunction "IO48_25") (pintype "bidirectional"))
    )
    (net (code "76") (name "unconnected-(U4-RXD0-Pad36)") (class "Default")
      (node (ref "U4") (pin "36") (pinfunction "RXD0_36") (pintype "bidirectional"))
    )
    (net (code "77") (name "unconnected-(U4-TXD0-Pad37)") (class "Default")
      (node (ref "U4") (pin "37") (pinfunction "TXD0_37") (pintype "bidirectional"))
    )
    (net (code "78") (name "unconnected-(U5-NC-Pad15)") (class "Default")
      (node (ref "U5") (pin "15") (pinfunction "NC_15") (pintype "no_connect"))
    )
  )
)
